# arcReactor.net
KiCad netlist of a schematic drawn in EAGLE
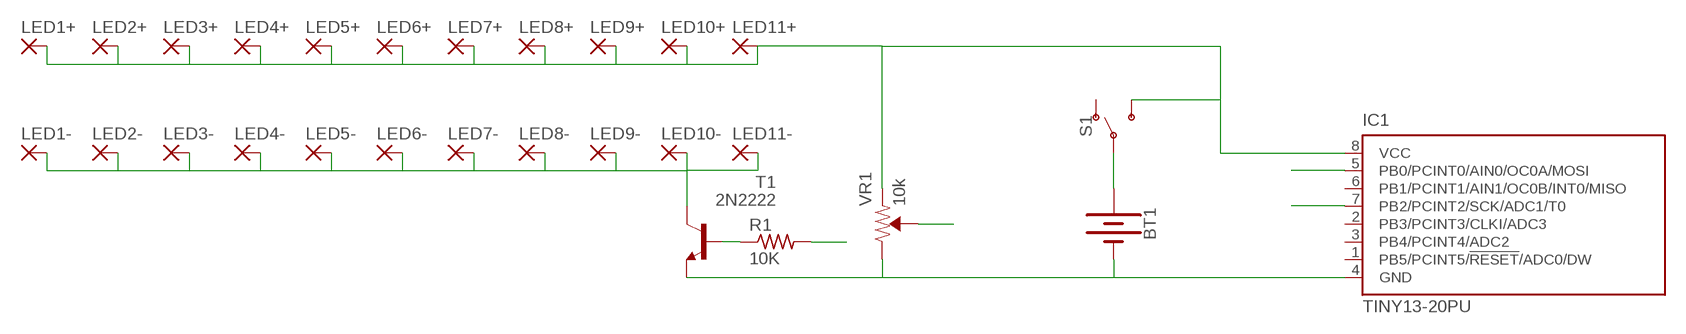
[diagram p0: schematic, sheet 1]

(export (version "E")
  (design (tool "Eeschema 10.0.6"))
  (components
    (comp (ref "BT1")
      (value "BATTERY-20MM_PTH")
      (footprint "eagle-import:BATTCOM_20MM_PTH")
      (libsource (lib "eagle-import") (part "BATTERY-20MM_PTH"))
    )
    (comp (ref "IC1")
      (value "TINY13-20PU")
      (footprint "eagle-import:DIL08")
      (fields (field (name "MPN") "ATTINY13-20PU"))
      (libsource (lib "eagle-import") (part "TINY13PU-20"))
    )
    (comp (ref "LED1+")
      (value "SMD2")
      (footprint "eagle-import:SMD1,27-2,54")
      (libsource (lib "eagle-import") (part "SMD2"))
    )
    (comp (ref "LED1-")
      (value "SMD2")
      (footprint "eagle-import:SMD1,27-2,54")
      (libsource (lib "eagle-import") (part "SMD2"))
    )
    (comp (ref "LED2+")
      (value "SMD2")
      (footprint "eagle-import:SMD1,27-2,54")
      (libsource (lib "eagle-import") (part "SMD2"))
    )
    (comp (ref "LED2-")
      (value "SMD2")
      (footprint "eagle-import:SMD1,27-2,54")
      (libsource (lib "eagle-import") (part "SMD2"))
    )
    (comp (ref "LED3+")
      (value "SMD2")
      (footprint "eagle-import:SMD1,27-2,54")
      (libsource (lib "eagle-import") (part "SMD2"))
    )
    (comp (ref "LED3-")
      (value "SMD2")
      (footprint "eagle-import:SMD1,27-2,54")
      (libsource (lib "eagle-import") (part "SMD2"))
    )
    (comp (ref "LED4+")
      (value "SMD2")
      (footprint "eagle-import:SMD1,27-2,54")
      (libsource (lib "eagle-import") (part "SMD2"))
    )
    (comp (ref "LED4-")
      (value "SMD2")
      (footprint "eagle-import:SMD1,27-2,54")
      (libsource (lib "eagle-import") (part "SMD2"))
    )
    (comp (ref "LED5+")
      (value "SMD2")
      (footprint "eagle-import:SMD1,27-2,54")
      (libsource (lib "eagle-import") (part "SMD2"))
    )
    (comp (ref "LED5-")
      (value "SMD2")
      (footprint "eagle-import:SMD1,27-2,54")
      (libsource (lib "eagle-import") (part "SMD2"))
    )
    (comp (ref "LED6+")
      (value "SMD2")
      (footprint "eagle-import:SMD1,27-2,54")
      (libsource (lib "eagle-import") (part "SMD2"))
    )
    (comp (ref "LED6-")
      (value "SMD2")
      (footprint "eagle-import:SMD1,27-2,54")
      (libsource (lib "eagle-import") (part "SMD2"))
    )
    (comp (ref "LED7+")
      (value "SMD2")
      (footprint "eagle-import:SMD1,27-2,54")
      (libsource (lib "eagle-import") (part "SMD2"))
    )
    (comp (ref "LED7-")
      (value "SMD2")
      (footprint "eagle-import:SMD1,27-2,54")
      (libsource (lib "eagle-import") (part "SMD2"))
    )
    (comp (ref "LED8+")
      (value "SMD2")
      (footprint "eagle-import:SMD1,27-2,54")
      (libsource (lib "eagle-import") (part "SMD2"))
    )
    (comp (ref "LED8-")
      (value "SMD2")
      (footprint "eagle-import:SMD1,27-2,54")
      (libsource (lib "eagle-import") (part "SMD2"))
    )
    (comp (ref "LED9+")
      (value "SMD2")
      (footprint "eagle-import:SMD1,27-2,54")
      (libsource (lib "eagle-import") (part "SMD2"))
    )
    (comp (ref "LED9-")
      (value "SMD2")
      (footprint "eagle-import:SMD1,27-2,54")
      (libsource (lib "eagle-import") (part "SMD2"))
    )
    (comp (ref "LED10+")
      (value "SMD2")
      (footprint "eagle-import:SMD1,27-2,54")
      (libsource (lib "eagle-import") (part "SMD2"))
    )
    (comp (ref "LED10-")
      (value "SMD2")
      (footprint "eagle-import:SMD1,27-2,54")
      (libsource (lib "eagle-import") (part "SMD2"))
    )
    (comp (ref "LED11+")
      (value "SMD2")
      (footprint "eagle-import:SMD1,27-2,54")
      (libsource (lib "eagle-import") (part "SMD2"))
    )
    (comp (ref "LED11-")
      (value "SMD2")
      (footprint "eagle-import:SMD1,27-2,54")
      (libsource (lib "eagle-import") (part "SMD2"))
    )
    (comp (ref "R1")
      (value "10K")
      (footprint "eagle-import:0204V")
      (libsource (lib "eagle-import") (part "R-US_0204/2V"))
    )
    (comp (ref "S1")
      (value "SWITCH-SPDT-PTH-11.6X4.0MM")
      (footprint "eagle-import:SWITCH_SPDT_PTH_11.6X4.0MM")
      (libsource (lib "eagle-import") (part "SWITCH-SPDT-PTH-11.6X4.0MM"))
    )
    (comp (ref "T1")
      (value "2N2222")
      (footprint "eagle-import:TO92-EBC-OVAL")
      (libsource (lib "eagle-import") (part "2N2222"))
    )
    (comp (ref "VR1")
      (value "10k")
      (footprint "eagle-import:TRIMPOT-PTH-3386U")
      (libsource (lib "eagle-import") (part "TRIMPOT-PTH-10MM-KNOB-1/2W-10%"))
    )
  )
  (nets
    (net (code "1") (name "Net-(BT1-+)") (class "Default")
      (node (ref "BT1") (pin "1") (pinfunction "+_1") (pintype "power_in"))
      (node (ref "S1") (pin "2") (pinfunction "P_2") (pintype "passive"))
    )
    (net (code "2") (name "Net-(BT1--)") (class "Default")
      (node (ref "BT1") (pin "2") (pinfunction "-_2") (pintype "power_in"))
      (node (ref "IC1") (pin "4") (pinfunction "GND_4") (pintype "power_in"))
      (node (ref "T1") (pin "E") (pinfunction "E_E") (pintype "passive"))
      (node (ref "VR1") (pin "3") (pinfunction "CW_3") (pintype "passive"))
    )
    (net (code "3") (name "Net-(IC1-VCC)") (class "Default")
      (node (ref "IC1") (pin "8") (pinfunction "VCC_8") (pintype "power_in"))
      (node (ref "LED1+") (pin "1") (pinfunction "P_1") (pintype "passive"))
      (node (ref "LED10+") (pin "1") (pinfunction "P_1") (pintype "passive"))
      (node (ref "LED11+") (pin "1") (pinfunction "P_1") (pintype "passive"))
      (node (ref "LED2+") (pin "1") (pinfunction "P_1") (pintype "passive"))
      (node (ref "LED3+") (pin "1") (pinfunction "P_1") (pintype "passive"))
      (node (ref "LED4+") (pin "1") (pinfunction "P_1") (pintype "passive"))
      (node (ref "LED5+") (pin "1") (pinfunction "P_1") (pintype "passive"))
      (node (ref "LED6+") (pin "1") (pinfunction "P_1") (pintype "passive"))
      (node (ref "LED7+") (pin "1") (pinfunction "P_1") (pintype "passive"))
      (node (ref "LED8+") (pin "1") (pinfunction "P_1") (pintype "passive"))
      (node (ref "LED9+") (pin "1") (pinfunction "P_1") (pintype "passive"))
      (node (ref "S1") (pin "3") (pinfunction "S_3") (pintype "passive"))
      (node (ref "VR1") (pin "1") (pinfunction "CCW_1") (pintype "passive"))
    )
    (net (code "4") (name "Net-(LED1--P)") (class "Default")
      (node (ref "LED1-") (pin "1") (pinfunction "P_1") (pintype "passive"))
      (node (ref "LED10-") (pin "1") (pinfunction "P_1") (pintype "passive"))
      (node (ref "LED11-") (pin "1") (pinfunction "P_1") (pintype "passive"))
      (node (ref "LED2-") (pin "1") (pinfunction "P_1") (pintype "passive"))
      (node (ref "LED3-") (pin "1") (pinfunction "P_1") (pintype "passive"))
      (node (ref "LED4-") (pin "1") (pinfunction "P_1") (pintype "passive"))
      (node (ref "LED5-") (pin "1") (pinfunction "P_1") (pintype "passive"))
      (node (ref "LED6-") (pin "1") (pinfunction "P_1") (pintype "passive"))
      (node (ref "LED7-") (pin "1") (pinfunction "P_1") (pintype "passive"))
      (node (ref "LED8-") (pin "1") (pinfunction "P_1") (pintype "passive"))
      (node (ref "LED9-") (pin "1") (pinfunction "P_1") (pintype "passive"))
      (node (ref "T1") (pin "C") (pinfunction "C_C") (pintype "passive"))
    )
    (net (code "5") (name "Net-(R1-Pad1)") (class "Default")
      (node (ref "R1") (pin "1") (pinfunction "1_1") (pintype "passive"))
      (node (ref "T1") (pin "B") (pinfunction "B_B") (pintype "passive"))
    )
    (net (code "6") (name "POTSENSE") (class "Default")
      (node (ref "IC1") (pin "7") (pinfunction "PB2/PCINT2/SCK/ADC1/T0_7") (pintype "bidirectional"))
      (node (ref "VR1") (pin "2") (pinfunction "WIPER_2") (pintype "passive"))
    )
    (net (code "7") (name "PWMCTRL") (class "Default")
      (node (ref "IC1") (pin "5") (pinfunction "PB0/PCINT0/AIN0/OC0A/MOSI_5") (pintype "bidirectional"))
      (node (ref "R1") (pin "2") (pinfunction "2_2") (pintype "passive"))
    )
    (net (code "8") (name "unconnected-(IC1-PB1{slash}PCINT1{slash}AIN1{slash}OC0B{slash}INT0{slash}MISO-Pad6)") (class "Default")
      (node (ref "IC1") (pin "6") (pinfunction "PB1/PCINT1/AIN1/OC0B/INT0/MISO_6") (pintype "bidirectional"))
    )
    (net (code "9") (name "unconnected-(IC1-PB3{slash}PCINT3{slash}CLKI{slash}ADC3-Pad2)") (class "Default")
      (node (ref "IC1") (pin "2") (pinfunction "PB3/PCINT3/CLKI/ADC3_2") (pintype "bidirectional"))
    )
    (net (code "10") (name "unconnected-(IC1-PB4{slash}PCINT4{slash}ADC2-Pad3)") (class "Default")
      (node (ref "IC1") (pin "3") (pinfunction "PB4/PCINT4/ADC2_3") (pintype "bidirectional"))
    )
    (net (code "11") (name "unconnected-(IC1-PB5{slash}PCINT5{slash}~{RESET}{slash}ADC0{slash}DW-Pad1)") (class "Default")
      (node (ref "IC1") (pin "1") (pinfunction "PB5/PCINT5/~{RESET}/ADC0/DW_1") (pintype "bidirectional"))
    )
    (net (code "12") (name "unconnected-(S1-O-Pad1)") (class "Default")
      (node (ref "S1") (pin "1") (pinfunction "O_1") (pintype "passive"))
    )
  )
)
